# SCH_Urinometer.net
KiCad netlist of a schematic drawn in EasyEDA
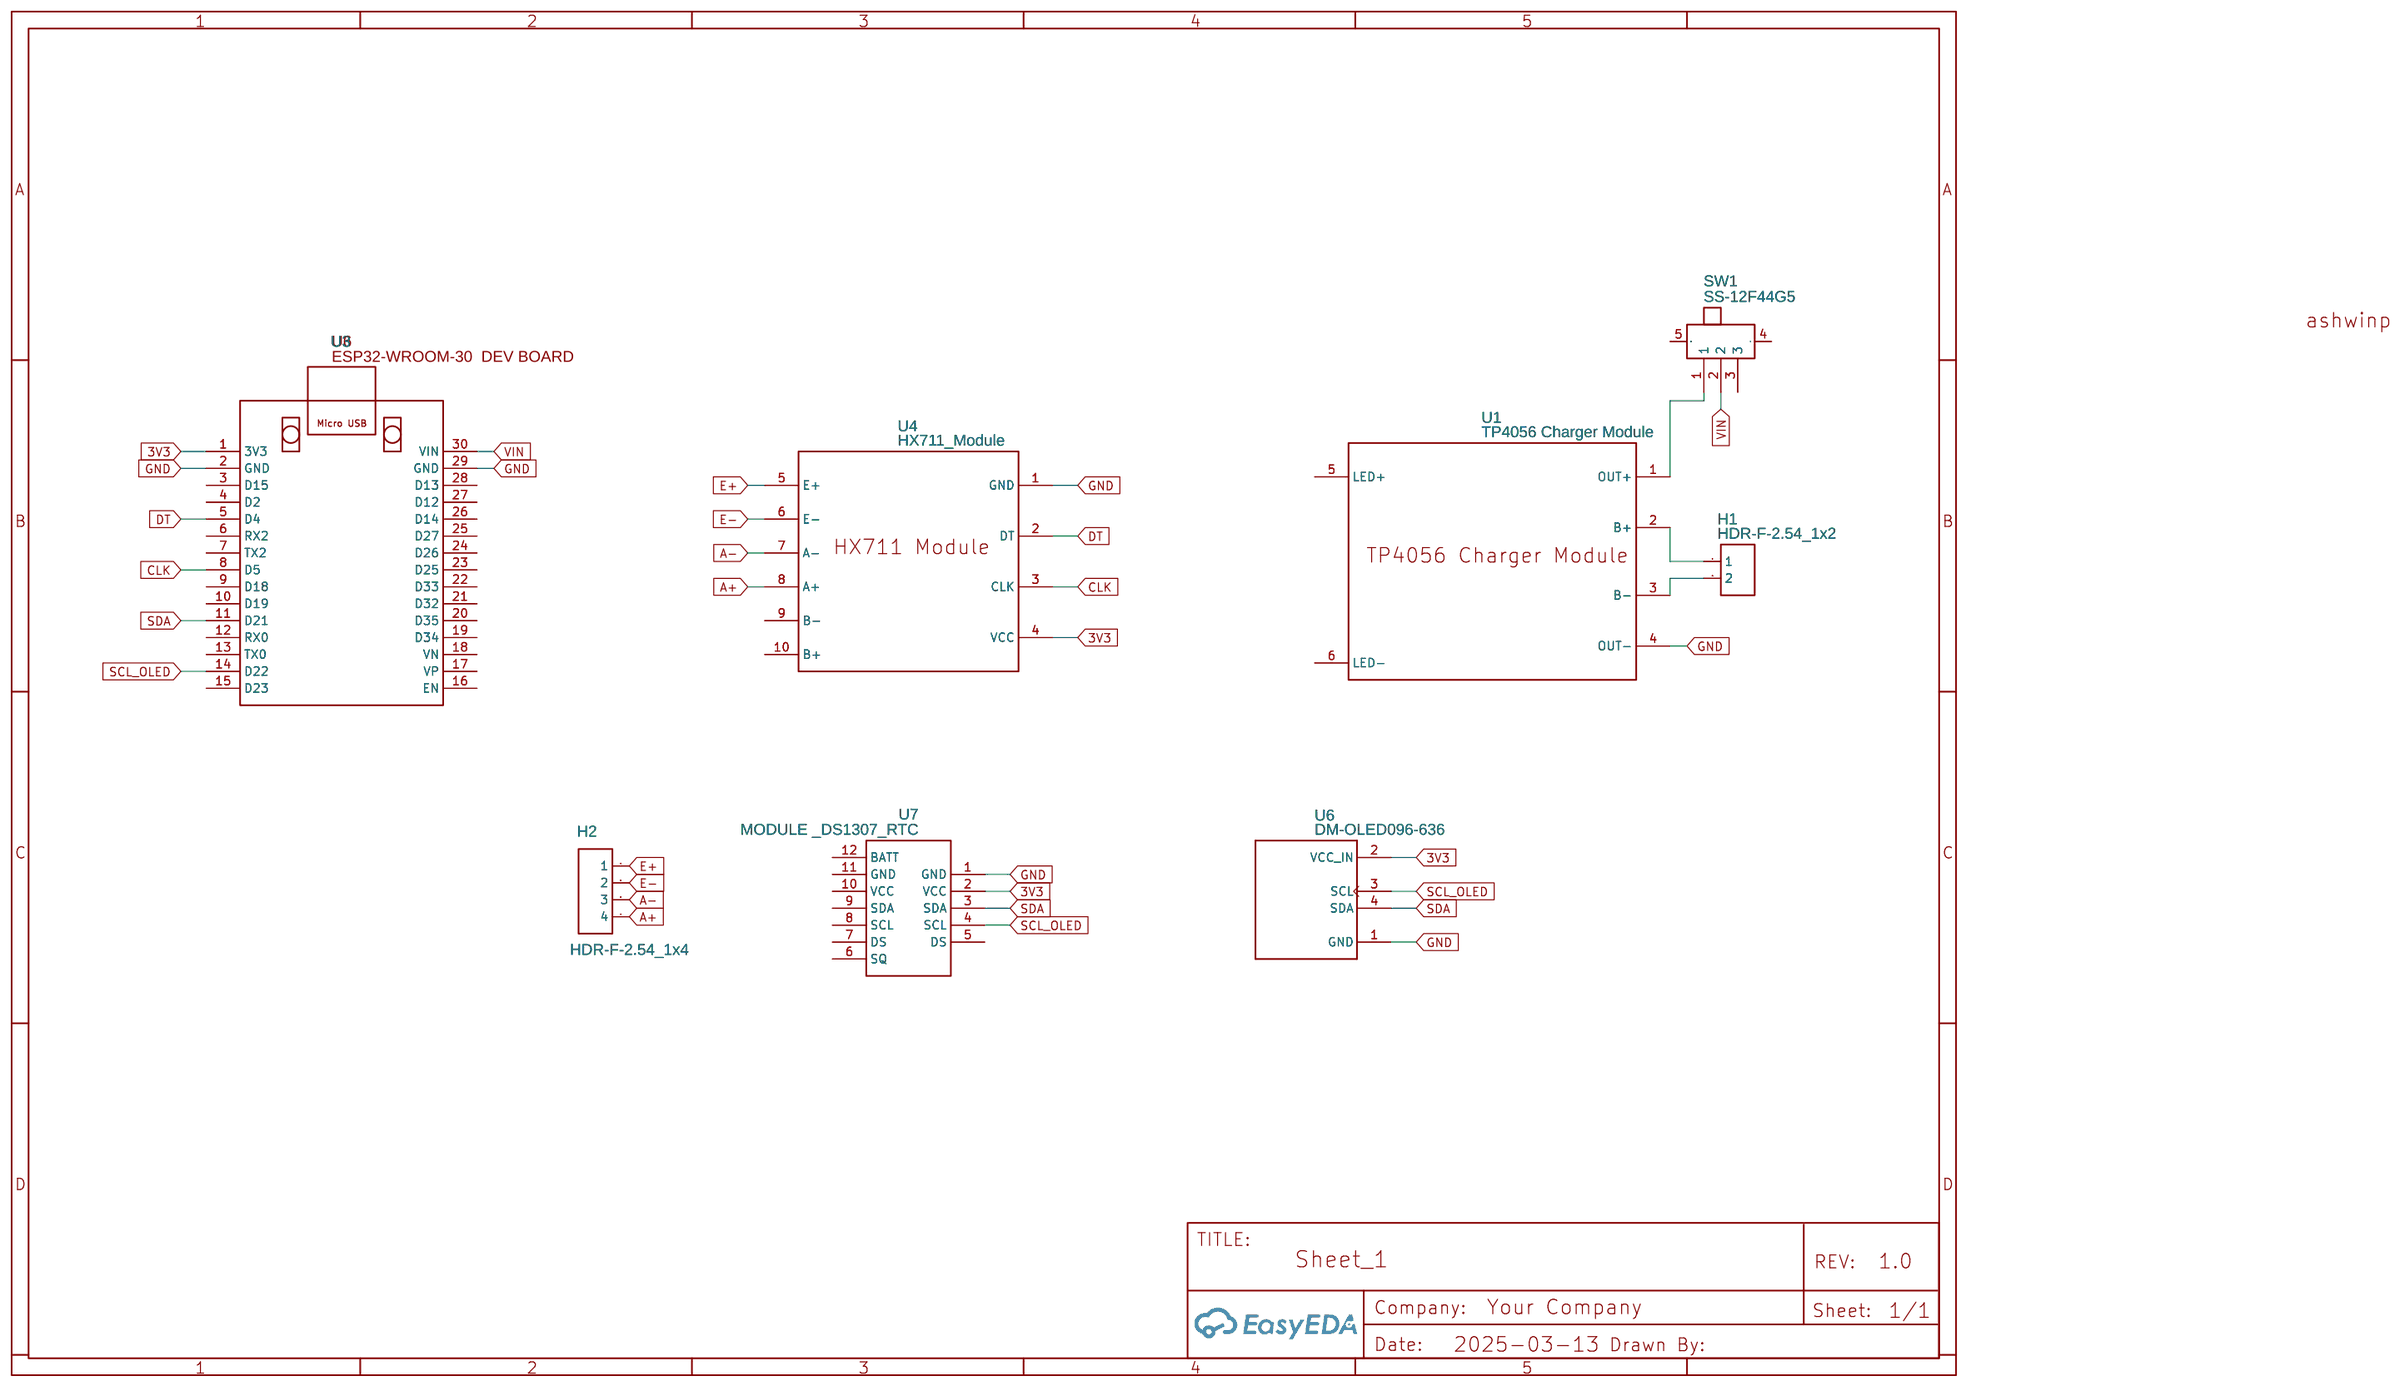
[diagram p0: schematic sheet]

(export (version "E")
  (design (tool "Eeschema 10.0.6"))
  (components
    (comp (ref "H1") (value "HDR-F-2.54_1x2") (libsource (lib "") (part "HDR-F-2.54_1x2")))
    (comp (ref "H2") (value "HDR-F-2.54_1x4") (libsource (lib "") (part "HDR-F-2.54_1x4")))
    (comp (ref "SW1")
      (value "SS-12F44G5")
      (fields (field (name "Manufacturer") "SOFNG(硕方)"))
      (libsource (lib "") (part "SS-12F44G5"))
    )
    (comp (ref "U1") (value "TP4056 Charger Module") (libsource (lib "") (part "TP4056 Charger Module")))
    (comp (ref "U3")
      (value "ESP32-WROOM 30-pin dev board for urinometer v2")
      (libsource (lib "") (part "ESP32-WROOM 30-pin dev board for urinometer v2"))
    )
    (comp (ref "U4") (value "HX711_Module") (libsource (lib "") (part "HX711_Module")))
    (comp (ref "U6") (value "DM-OLED096-636") (libsource (lib "") (part "DM-OLED096-636")))
    (comp (ref "U7") (value "MODULE _DS1307_RTC") (libsource (lib "") (part "MODULE _DS1307_RTC")))
  )
  (nets
    (net (code "1") (name "3V3") (class "Default")
      (node (ref "U3") (pin "1") (pinfunction "3V3_1") (pintype "unspecified"))
      (node (ref "U4") (pin "4") (pinfunction "VCC_4") (pintype "unspecified"))
      (node (ref "U6") (pin "2") (pinfunction "VCC_IN_2") (pintype "bidirectional"))
      (node (ref "U7") (pin "2") (pinfunction "VCC_2") (pintype "unspecified"))
    )
    (net (code "2") (name "A+") (class "Default")
      (node (ref "H2") (pin "4") (pinfunction "4_4") (pintype "unspecified"))
      (node (ref "U4") (pin "8") (pinfunction "A+_8") (pintype "unspecified"))
    )
    (net (code "3") (name "A-") (class "Default")
      (node (ref "H2") (pin "3") (pinfunction "3_3") (pintype "unspecified"))
      (node (ref "U4") (pin "7") (pinfunction "A-_7") (pintype "unspecified"))
    )
    (net (code "4") (name "CLK") (class "Default")
      (node (ref "U3") (pin "8") (pinfunction "D5_8") (pintype "unspecified"))
      (node (ref "U4") (pin "3") (pinfunction "CLK_3") (pintype "unspecified"))
    )
    (net (code "5") (name "DT") (class "Default")
      (node (ref "U3") (pin "5") (pinfunction "D4_5") (pintype "unspecified"))
      (node (ref "U4") (pin "2") (pinfunction "DT_2") (pintype "unspecified"))
    )
    (net (code "6") (name "E+") (class "Default")
      (node (ref "H2") (pin "1") (pinfunction "1_1") (pintype "unspecified"))
      (node (ref "U4") (pin "5") (pinfunction "E+_5") (pintype "unspecified"))
    )
    (net (code "7") (name "E-") (class "Default")
      (node (ref "H2") (pin "2") (pinfunction "2_2") (pintype "unspecified"))
      (node (ref "U4") (pin "6") (pinfunction "E-_6") (pintype "unspecified"))
    )
    (net (code "8") (name "GND") (class "Default")
      (node (ref "U1") (pin "4") (pinfunction "OUT-_4") (pintype "unspecified"))
      (node (ref "U3") (pin "2") (pinfunction "GND_2") (pintype "unspecified"))
      (node (ref "U3") (pin "29") (pinfunction "GND_29") (pintype "unspecified"))
      (node (ref "U4") (pin "1") (pinfunction "GND_1") (pintype "unspecified"))
      (node (ref "U6") (pin "1") (pinfunction "GND_1") (pintype "bidirectional"))
      (node (ref "U7") (pin "1") (pinfunction "GND_1") (pintype "unspecified"))
    )
    (net (code "9") (name "Net-(U1-B+)") (class "Default")
      (node (ref "H1") (pin "1") (pinfunction "1_1") (pintype "input"))
      (node (ref "U1") (pin "2") (pinfunction "B+_2") (pintype "unspecified"))
    )
    (net (code "10") (name "Net-(U1-B-)") (class "Default")
      (node (ref "H1") (pin "2") (pinfunction "2_2") (pintype "input"))
      (node (ref "U1") (pin "3") (pinfunction "B-_3") (pintype "unspecified"))
    )
    (net (code "11") (name "Net-(U1-OUT+)") (class "Default")
      (node (ref "SW1") (pin "1") (pinfunction "1_1") (pintype "unspecified"))
      (node (ref "U1") (pin "1") (pinfunction "OUT+_1") (pintype "unspecified"))
    )
    (net (code "12") (name "SCL_OLED") (class "Default")
      (node (ref "U3") (pin "14") (pinfunction "D22_14") (pintype "unspecified"))
      (node (ref "U6") (pin "3") (pinfunction "SCL_3") (pintype "bidirectional"))
      (node (ref "U7") (pin "4") (pinfunction "SCL_4") (pintype "unspecified"))
    )
    (net (code "13") (name "SDA") (class "Default")
      (node (ref "U3") (pin "11") (pinfunction "D21_11") (pintype "unspecified"))
      (node (ref "U6") (pin "4") (pinfunction "SDA_4") (pintype "bidirectional"))
      (node (ref "U7") (pin "3") (pinfunction "SDA_3") (pintype "unspecified"))
    )
    (net (code "14") (name "VIN") (class "Default")
      (node (ref "SW1") (pin "2") (pinfunction "2_2") (pintype "unspecified"))
      (node (ref "U3") (pin "30") (pinfunction "VIN_30") (pintype "unspecified"))
    )
    (net (code "15") (name "unconnected-(SW1-Pad3)") (class "Default")
      (node (ref "SW1") (pin "3") (pinfunction "3_3") (pintype "unspecified"))
    )
    (net (code "16") (name "unconnected-(SW1-Pad4)") (class "Default")
      (node (ref "SW1") (pin "4") (pinfunction "4_4") (pintype "unspecified"))
    )
    (net (code "17") (name "unconnected-(SW1-Pad5)") (class "Default")
      (node (ref "SW1") (pin "5") (pinfunction "5_5") (pintype "unspecified"))
    )
    (net (code "18") (name "unconnected-(U1-LED+-Pad5)") (class "Default")
      (node (ref "U1") (pin "5") (pinfunction "LED+_5") (pintype "unspecified"))
    )
    (net (code "19") (name "unconnected-(U1-LED--Pad6)") (class "Default")
      (node (ref "U1") (pin "6") (pinfunction "LED-_6") (pintype "unspecified"))
    )
    (net (code "20") (name "unconnected-(U3-D2-Pad4)") (class "Default")
      (node (ref "U3") (pin "4") (pinfunction "D2_4") (pintype "unspecified"))
    )
    (net (code "21") (name "unconnected-(U3-D12-Pad27)") (class "Default")
      (node (ref "U3") (pin "27") (pinfunction "D12_27") (pintype "unspecified"))
    )
    (net (code "22") (name "unconnected-(U3-D13-Pad28)") (class "Default")
      (node (ref "U3") (pin "28") (pinfunction "D13_28") (pintype "unspecified"))
    )
    (net (code "23") (name "unconnected-(U3-D14-Pad26)") (class "Default")
      (node (ref "U3") (pin "26") (pinfunction "D14_26") (pintype "unspecified"))
    )
    (net (code "24") (name "unconnected-(U3-D15-Pad3)") (class "Default")
      (node (ref "U3") (pin "3") (pinfunction "D15_3") (pintype "unspecified"))
    )
    (net (code "25") (name "unconnected-(U3-D18-Pad9)") (class "Default")
      (node (ref "U3") (pin "9") (pinfunction "D18_9") (pintype "unspecified"))
    )
    (net (code "26") (name "unconnected-(U3-D19-Pad10)") (class "Default")
      (node (ref "U3") (pin "10") (pinfunction "D19_10") (pintype "unspecified"))
    )
    (net (code "27") (name "unconnected-(U3-D23-Pad15)") (class "Default")
      (node (ref "U3") (pin "15") (pinfunction "D23_15") (pintype "unspecified"))
    )
    (net (code "28") (name "unconnected-(U3-D25-Pad23)") (class "Default")
      (node (ref "U3") (pin "23") (pinfunction "D25_23") (pintype "unspecified"))
    )
    (net (code "29") (name "unconnected-(U3-D26-Pad24)") (class "Default")
      (node (ref "U3") (pin "24") (pinfunction "D26_24") (pintype "unspecified"))
    )
    (net (code "30") (name "unconnected-(U3-D27-Pad25)") (class "Default")
      (node (ref "U3") (pin "25") (pinfunction "D27_25") (pintype "unspecified"))
    )
    (net (code "31") (name "unconnected-(U3-D32-Pad21)") (class "Default")
      (node (ref "U3") (pin "21") (pinfunction "D32_21") (pintype "unspecified"))
    )
    (net (code "32") (name "unconnected-(U3-D33-Pad22)") (class "Default")
      (node (ref "U3") (pin "22") (pinfunction "D33_22") (pintype "unspecified"))
    )
    (net (code "33") (name "unconnected-(U3-D34-Pad19)") (class "Default")
      (node (ref "U3") (pin "19") (pinfunction "D34_19") (pintype "unspecified"))
    )
    (net (code "34") (name "unconnected-(U3-D35-Pad20)") (class "Default")
      (node (ref "U3") (pin "20") (pinfunction "D35_20") (pintype "unspecified"))
    )
    (net (code "35") (name "unconnected-(U3-EN-Pad16)") (class "Default")
      (node (ref "U3") (pin "16") (pinfunction "EN_16") (pintype "unspecified"))
    )
    (net (code "36") (name "unconnected-(U3-RX0-Pad12)") (class "Default")
      (node (ref "U3") (pin "12") (pinfunction "RX0_12") (pintype "unspecified"))
    )
    (net (code "37") (name "unconnected-(U3-RX2-Pad6)") (class "Default")
      (node (ref "U3") (pin "6") (pinfunction "RX2_6") (pintype "unspecified"))
    )
    (net (code "38") (name "unconnected-(U3-TX0-Pad13)") (class "Default")
      (node (ref "U3") (pin "13") (pinfunction "TX0_13") (pintype "unspecified"))
    )
    (net (code "39") (name "unconnected-(U3-TX2-Pad7)") (class "Default")
      (node (ref "U3") (pin "7") (pinfunction "TX2_7") (pintype "unspecified"))
    )
    (net (code "40") (name "unconnected-(U3-VN-Pad18)") (class "Default")
      (node (ref "U3") (pin "18") (pinfunction "VN_18") (pintype "unspecified"))
    )
    (net (code "41") (name "unconnected-(U3-VP-Pad17)") (class "Default")
      (node (ref "U3") (pin "17") (pinfunction "VP_17") (pintype "unspecified"))
    )
    (net (code "42") (name "unconnected-(U4-B+-Pad10)") (class "Default")
      (node (ref "U4") (pin "10") (pinfunction "B+_10") (pintype "unspecified"))
    )
    (net (code "43") (name "unconnected-(U4-B--Pad9)") (class "Default")
      (node (ref "U4") (pin "9") (pinfunction "B-_9") (pintype "unspecified"))
    )
    (net (code "44") (name "unconnected-(U7-BATT-Pad12)") (class "Default")
      (node (ref "U7") (pin "12") (pinfunction "BATT_12") (pintype "unspecified"))
    )
    (net (code "45") (name "unconnected-(U7-DS-Pad5)") (class "Default")
      (node (ref "U7") (pin "5") (pinfunction "DS_5") (pintype "unspecified"))
    )
    (net (code "46") (name "unconnected-(U7-DS-Pad7)") (class "Default")
      (node (ref "U7") (pin "7") (pinfunction "DS_7") (pintype "unspecified"))
    )
    (net (code "47") (name "unconnected-(U7-GND-Pad11)") (class "Default")
      (node (ref "U7") (pin "11") (pinfunction "GND_11") (pintype "unspecified"))
    )
    (net (code "48") (name "unconnected-(U7-SCL-Pad8)") (class "Default")
      (node (ref "U7") (pin "8") (pinfunction "SCL_8") (pintype "unspecified"))
    )
    (net (code "49") (name "unconnected-(U7-SDA-Pad9)") (class "Default")
      (node (ref "U7") (pin "9") (pinfunction "SDA_9") (pintype "unspecified"))
    )
    (net (code "50") (name "unconnected-(U7-SQ-Pad6)") (class "Default")
      (node (ref "U7") (pin "6") (pinfunction "SQ_6") (pintype "unspecified"))
    )
    (net (code "51") (name "unconnected-(U7-VCC-Pad10)") (class "Default")
      (node (ref "U7") (pin "10") (pinfunction "VCC_10") (pintype "unspecified"))
    )
  )
)
